# LAN9254_A_P1.net
KiCad netlist of a schematic drawn in Altium Designer
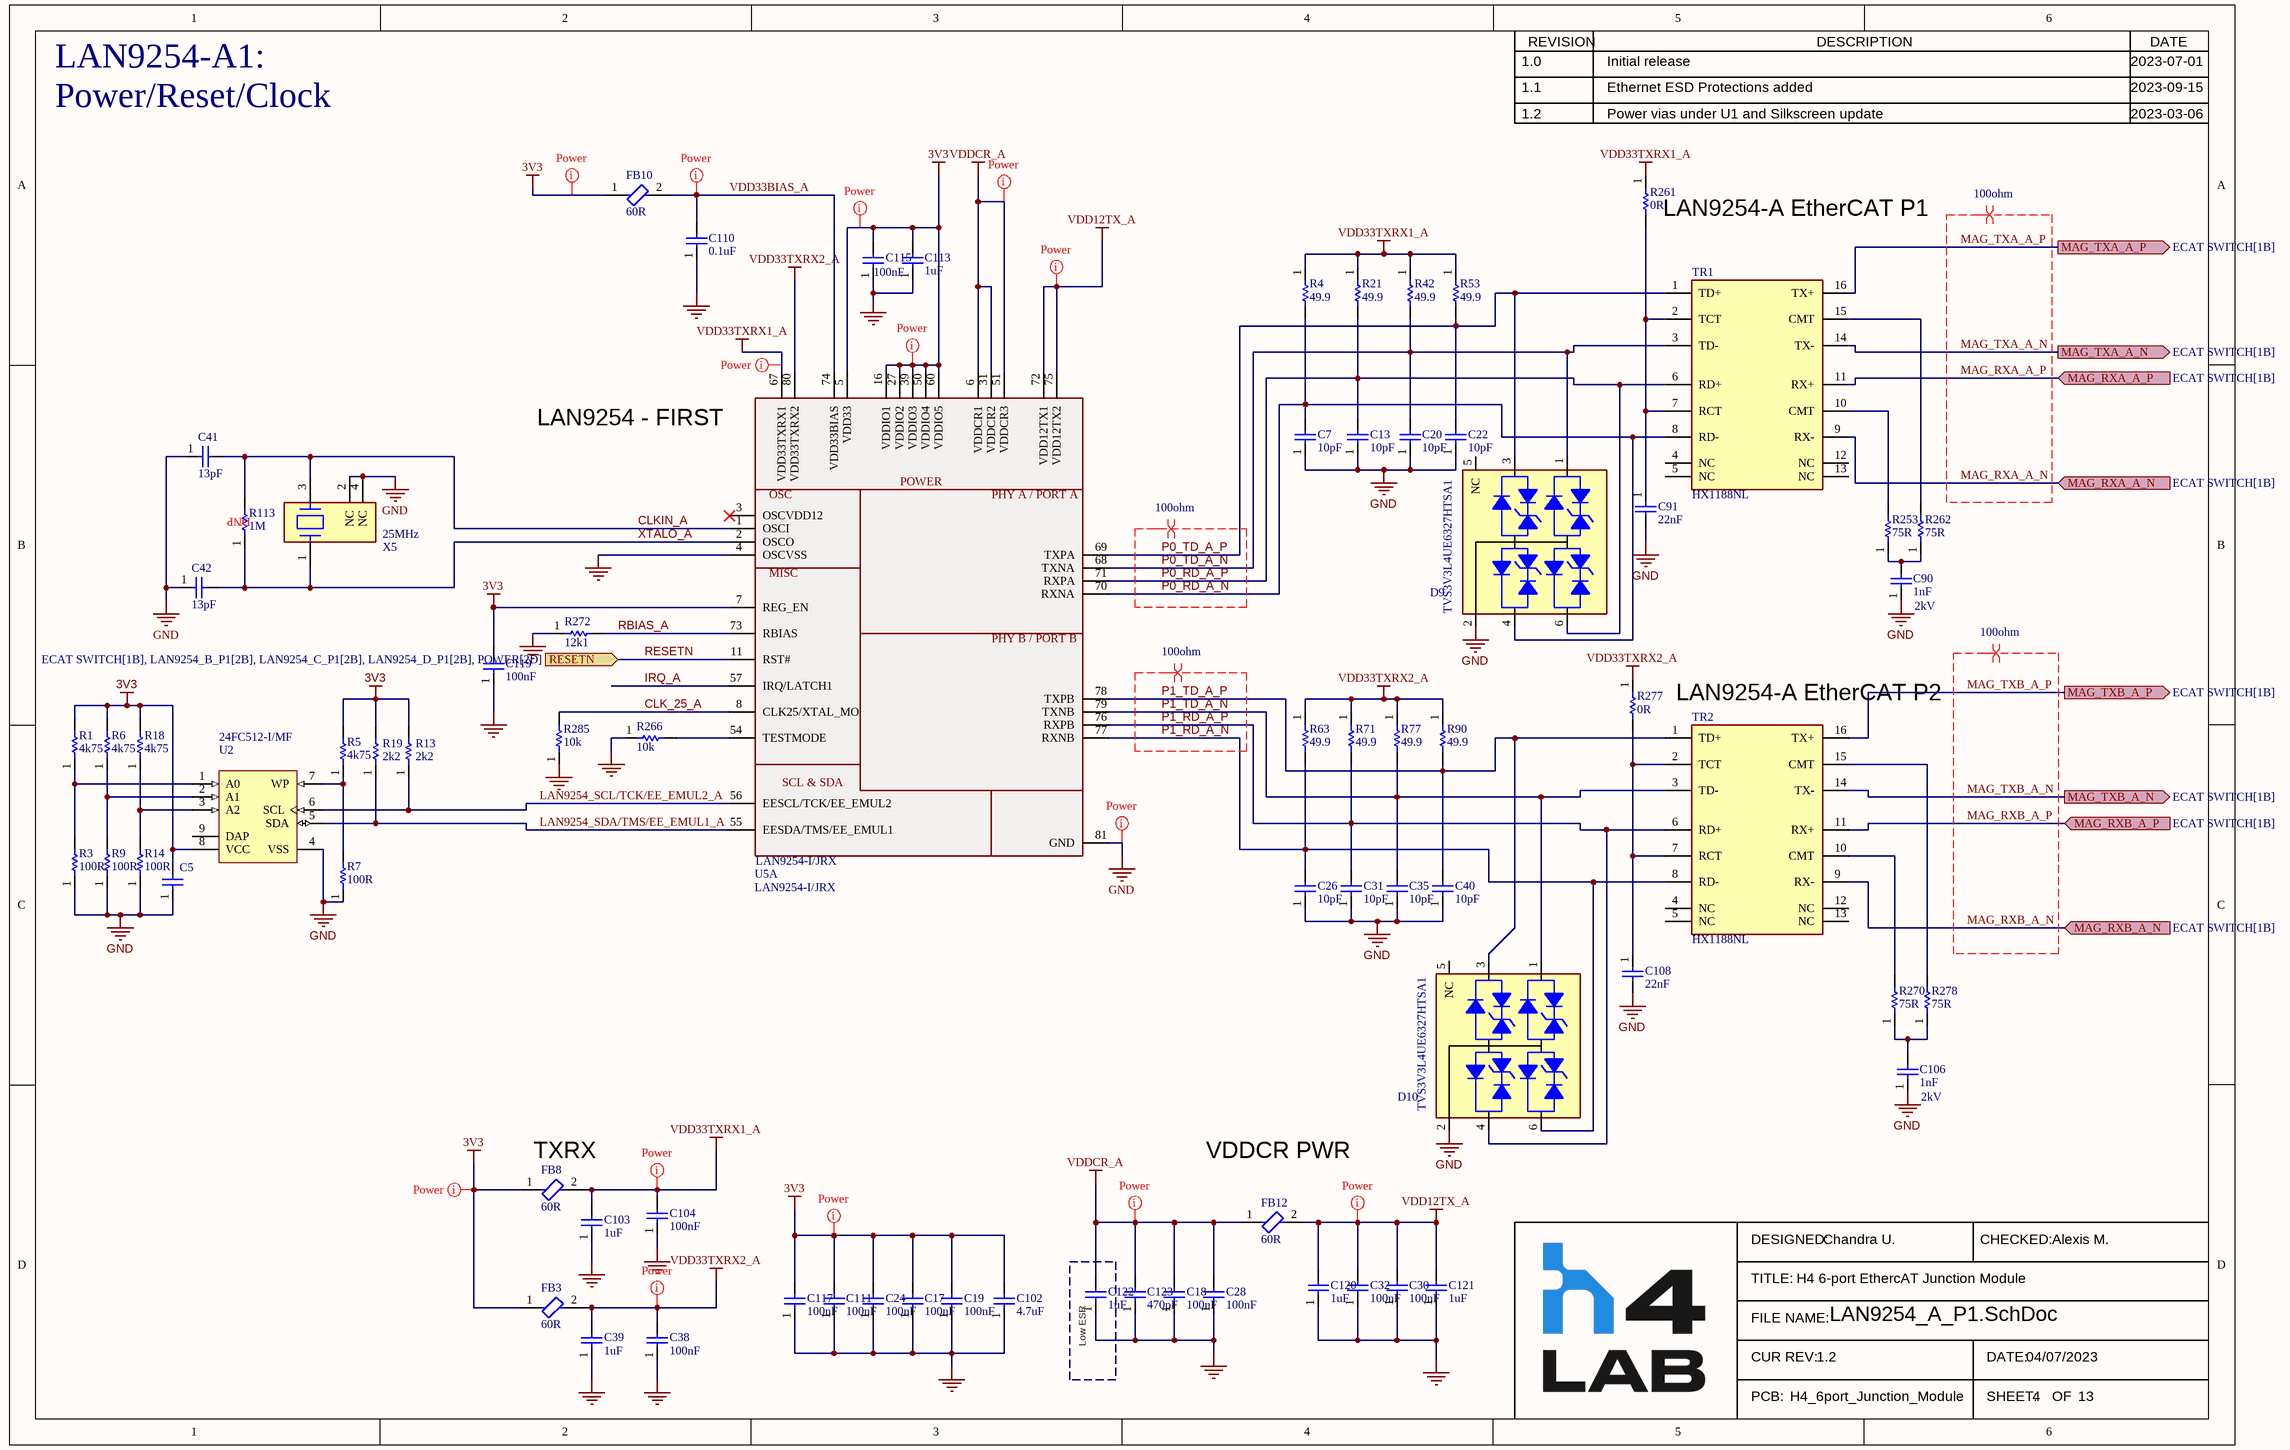
[diagram p0: LAN9254_A_P1.SchDoc]

(export (version "E")
  (design (tool "Eeschema 10.0.6"))
  (components
    (comp (ref "C5")
      (value "GRM155R71C104JA88D")
      (footprint "CAPC1005X03N(0402)")
      (description "CAP CER 0.1UF 16V X7R 0402")
      (fields (field (name "TOLERANCE") "5%"))
      (libsource (lib "IHMC_Altium_Lib") (part "100nF_16V_0402_CAP"))
    )
    (comp (ref "C7")
      (value "10pF")
      (footprint "0402_C")
      (description "Cap Ceramic 10pF 50V C0G 5% SMD 0402 125°C Punched Paper T/R")
      (fields (field (name "TOLERANCE") "5%") (field (name "MANUFACTURER") "KEMET"))
      (libsource (lib "IHMC_Altium_Lib") (part "10pF_50V_0402_C0402C100J5GAC7411"))
    )
    (comp (ref "C13")
      (value "10pF")
      (footprint "0402_C")
      (description "Cap Ceramic 10pF 50V C0G 5% SMD 0402 125°C Punched Paper T/R")
      (fields (field (name "TOLERANCE") "5%") (field (name "MANUFACTURER") "KEMET"))
      (libsource (lib "IHMC_Altium_Lib") (part "10pF_50V_0402_C0402C100J5GAC7411"))
    )
    (comp (ref "C17")
      (value "100nF")
      (footprint "CAPC1005X03N(0402)")
      (description "CAP CER 0.1UF 16V X7R 0402")
      (fields (field (name "MPN") "GRM155R71C104JA88D") (field (name "TOLERANCE") "5%"))
      (libsource (lib "IHMC_Altium_Lib") (part "100nF_16V_0402_CAP"))
    )
    (comp (ref "C18")
      (value "100nF")
      (footprint "CAPC1005X03N(0402)")
      (description "CAP CER 0.1UF 16V X7R 0402")
      (fields (field (name "MPN") "GRM155R71C104JA88D") (field (name "TOLERANCE") "5%"))
      (libsource (lib "IHMC_Altium_Lib") (part "100nF_16V_0402_CAP"))
    )
    (comp (ref "C19")
      (value "100nF")
      (footprint "CAPC1005X03N(0402)")
      (description "CAP CER 0.1UF 16V X7R 0402")
      (fields (field (name "MPN") "GRM155R71C104JA88D") (field (name "TOLERANCE") "5%"))
      (libsource (lib "IHMC_Altium_Lib") (part "100nF_16V_0402_CAP"))
    )
    (comp (ref "C20")
      (value "10pF")
      (footprint "0402_C")
      (description "Cap Ceramic 10pF 50V C0G 5% SMD 0402 125°C Punched Paper T/R")
      (fields (field (name "TOLERANCE") "5%") (field (name "MANUFACTURER") "KEMET"))
      (libsource (lib "IHMC_Altium_Lib") (part "10pF_50V_0402_C0402C100J5GAC7411"))
    )
    (comp (ref "C22")
      (value "10pF")
      (footprint "0402_C")
      (description "Cap Ceramic 10pF 50V C0G 5% SMD 0402 125°C Punched Paper T/R")
      (fields (field (name "TOLERANCE") "5%") (field (name "MANUFACTURER") "KEMET"))
      (libsource (lib "IHMC_Altium_Lib") (part "10pF_50V_0402_C0402C100J5GAC7411"))
    )
    (comp (ref "C24")
      (value "100nF")
      (footprint "CAPC1005X03N(0402)")
      (description "CAP CER 0.1UF 16V X7R 0402")
      (fields (field (name "MPN") "GRM155R71C104JA88D") (field (name "TOLERANCE") "5%"))
      (libsource (lib "IHMC_Altium_Lib") (part "100nF_16V_0402_CAP"))
    )
    (comp (ref "C26")
      (value "10pF")
      (footprint "0402_C")
      (description "Cap Ceramic 10pF 50V C0G 5% SMD 0402 125°C Punched Paper T/R")
      (fields (field (name "TOLERANCE") "5%") (field (name "MANUFACTURER") "KEMET"))
      (libsource (lib "IHMC_Altium_Lib") (part "10pF_50V_0402_C0402C100J5GAC7411"))
    )
    (comp (ref "C28")
      (value "100nF")
      (footprint "CAPC1005X03N(0402)")
      (description "CAP CER 0.1UF 16V X7R 0402")
      (fields (field (name "MPN") "GRM155R71C104JA88D") (field (name "TOLERANCE") "5%"))
      (libsource (lib "IHMC_Altium_Lib") (part "100nF_16V_0402_CAP"))
    )
    (comp (ref "C30")
      (value "100nF")
      (footprint "CAPC1005X03N(0402)")
      (description "CAP CER 0.1UF 16V X7R 0402")
      (fields (field (name "MPN") "GRM155R71C104JA88D") (field (name "TOLERANCE") "5%"))
      (libsource (lib "IHMC_Altium_Lib") (part "100nF_16V_0402_CAP"))
    )
    (comp (ref "C31")
      (value "10pF")
      (footprint "0402_C")
      (description "Cap Ceramic 10pF 50V C0G 5% SMD 0402 125°C Punched Paper T/R")
      (fields (field (name "TOLERANCE") "5%") (field (name "MANUFACTURER") "KEMET"))
      (libsource (lib "IHMC_Altium_Lib") (part "10pF_50V_0402_C0402C100J5GAC7411"))
    )
    (comp (ref "C32")
      (value "100nF")
      (footprint "CAPC1005X03N(0402)")
      (description "CAP CER 0.1UF 16V X7R 0402")
      (fields (field (name "MPN") "GRM155R71C104JA88D") (field (name "TOLERANCE") "5%"))
      (libsource (lib "IHMC_Altium_Lib") (part "100nF_16V_0402_CAP"))
    )
    (comp (ref "C35")
      (value "10pF")
      (footprint "0402_C")
      (description "Cap Ceramic 10pF 50V C0G 5% SMD 0402 125°C Punched Paper T/R")
      (fields (field (name "TOLERANCE") "5%") (field (name "MANUFACTURER") "KEMET"))
      (libsource (lib "IHMC_Altium_Lib") (part "10pF_50V_0402_C0402C100J5GAC7411"))
    )
    (comp (ref "C38")
      (value "100nF")
      (footprint "CAPC1005X03N(0402)")
      (description "CAP CER 0.1UF 16V X7R 0402")
      (fields (field (name "MPN") "GRM155R71C104JA88D") (field (name "TOLERANCE") "5%"))
      (libsource (lib "IHMC_Altium_Lib") (part "100nF_16V_0402_CAP"))
    )
    (comp (ref "C39")
      (value "1uF")
      (footprint "CAPC1608X09N(0603)")
      (description "MLCC - SMD/SMT 25volts 1uF X5R 10%")
      (fields
        (field (name "MPN") "C0603C105K3PACTU")
        (field (name "VOLTAGE") "25VDC")
        (field (name "DRAWN BY") "TC")
      )
      (libsource (lib "IHMC_Altium_Lib") (part "1uF_25VDC_0603_Cap"))
    )
    (comp (ref "C40")
      (value "10pF")
      (footprint "0402_C")
      (description "Cap Ceramic 10pF 50V C0G 5% SMD 0402 125°C Punched Paper T/R")
      (fields (field (name "TOLERANCE") "5%") (field (name "MANUFACTURER") "KEMET"))
      (libsource (lib "IHMC_Altium_Lib") (part "10pF_50V_0402_C0402C100J5GAC7411"))
    )
    (comp (ref "C41")
      (value "13pF")
      (footprint "0402_C")
      (description "Cap Ceramic Monolithic 13pF 50VDC 2% SMD Emboss T/R")
      (fields
        (field (name "MANUFACTURER") "Murata")
        (field (name "MANUFACTURER PART NUMBER") "GRM0225C1H130GA03L")
      )
      (libsource (lib "IHMC_Capacitors") (part "13pF_50V_0402_CAP_GRM0225C1H130GA03L"))
    )
    (comp (ref "C42")
      (value "13pF")
      (footprint "0402_C")
      (description "Cap Ceramic Monolithic 13pF 50VDC 2% SMD Emboss T/R")
      (fields
        (field (name "MANUFACTURER") "Murata")
        (field (name "MANUFACTURER PART NUMBER") "GRM0225C1H130GA03L")
      )
      (libsource (lib "IHMC_Capacitors") (part "13pF_50V_0402_CAP_GRM0225C1H130GA03L"))
    )
    (comp (ref "C90")
      (value "1nF")
      (footprint "CAPC3216X16N(1206)")
      (description "CAP CER 1000PF 2KV X7R 1206")
      (fields
        (field (name "VOLTAGE RATING") "2kV")
        (field (name "TOLERANCE") "10%")
        (field (name "MPN") "CC1206KKX7RDBB102")
      )
      (libsource (lib "IHMC_Altium_Lib") (part "1nF_2kV_1206_CAP"))
    )
    (comp (ref "C91")
      (value "22nF")
      (footprint "CAPC1005X03N(0402)")
      (description "CAP CER 0.022UF 50V X7R 0402")
      (fields (field (name "MPN") "GCM155R71H223KA55D") (field (name "TOLERANCE") "10%"))
      (libsource (lib "IHMC_Capacitors") (part "22nF_50V_0402_CAP"))
    )
    (comp (ref "C102")
      (value "4.7uF")
      (footprint "CAPC3216X16N(1206)")
      (description "CAP CER 4.7UF 50V X7R 1206")
      (fields (field (name "MPN") "CL31B475KBHNNNE") (field (name "TOLERANCE") "10%"))
      (libsource (lib "IHMC_Altium_Lib") (part "4.7uF_50V_1206_CAP"))
    )
    (comp (ref "C103")
      (value "1uF")
      (footprint "CAPC1608X09N(0603)")
      (description "MLCC - SMD/SMT 25volts 1uF X5R 10%")
      (fields
        (field (name "MPN") "C0603C105K3PACTU")
        (field (name "VOLTAGE") "25VDC")
        (field (name "DRAWN BY") "TC")
      )
      (libsource (lib "IHMC_Altium_Lib") (part "1uF_25VDC_0603_Cap"))
    )
    (comp (ref "C104")
      (value "100nF")
      (footprint "CAPC1005X03N(0402)")
      (description "CAP CER 0.1UF 16V X7R 0402")
      (fields (field (name "MPN") "GRM155R71C104JA88D") (field (name "TOLERANCE") "5%"))
      (libsource (lib "IHMC_Altium_Lib") (part "100nF_16V_0402_CAP"))
    )
    (comp (ref "C106")
      (value "1nF")
      (footprint "CAPC3216X16N(1206)")
      (description "CAP CER 1000PF 2KV X7R 1206")
      (fields
        (field (name "VOLTAGE RATING") "2kV")
        (field (name "TOLERANCE") "10%")
        (field (name "MPN") "CC1206KKX7RDBB102")
      )
      (libsource (lib "IHMC_Altium_Lib") (part "1nF_2kV_1206_CAP"))
    )
    (comp (ref "C108")
      (value "22nF")
      (footprint "CAPC1005X03N(0402)")
      (description "CAP CER 0.022UF 50V X7R 0402")
      (fields (field (name "MPN") "GCM155R71H223KA55D") (field (name "TOLERANCE") "10%"))
      (libsource (lib "IHMC_Capacitors") (part "22nF_50V_0402_CAP"))
    )
    (comp (ref "C110")
      (value "0.1uF")
      (footprint "CAPC1608X09N(0603)")
      (description "CAP CER 0.1UF 100V X7R 0603")
      (fields (field (name "MPN") "CL10B104KC8NNNC") (field (name "TOLERANCE") "10%"))
      (libsource (lib "IHMC_Altium_Lib") (part "0.1uF_100V_0603_CAP"))
    )
    (comp (ref "C111")
      (value "100nF")
      (footprint "CAPC1005X03N(0402)")
      (description "CAP CER 0.1UF 16V X7R 0402")
      (fields (field (name "MPN") "GRM155R71C104JA88D") (field (name "TOLERANCE") "5%"))
      (libsource (lib "IHMC_Altium_Lib") (part "100nF_16V_0402_CAP"))
    )
    (comp (ref "C113")
      (value "1uF")
      (footprint "0603_C")
      (description "Multilayer Ceramic Capacitors (High dielectric type), 10V, 1 uF, ± 10 %, 0603, X5R, RoHS")
      (fields (field (name "TOLERANCE") "10%") (field (name "MANUFACTURER") "Taiyo Yuden"))
      (libsource (lib "IHMC_Capacitors") (part "1uF_10V_low_ESR_0603_LMK107BJ105KA-T"))
    )
    (comp (ref "C115")
      (value "100nF")
      (footprint "CAPC1005X03N(0402)")
      (description "CAP CER 0.1UF 16V X7R 0402")
      (fields (field (name "MPN") "GRM155R71C104JA88D") (field (name "TOLERANCE") "5%"))
      (libsource (lib "IHMC_Altium_Lib") (part "100nF_16V_0402_CAP"))
    )
    (comp (ref "C117")
      (value "100nF")
      (footprint "CAPC1005X03N(0402)")
      (description "CAP CER 0.1UF 16V X7R 0402")
      (fields (field (name "MPN") "GRM155R71C104JA88D") (field (name "TOLERANCE") "5%"))
      (libsource (lib "IHMC_Altium_Lib") (part "100nF_16V_0402_CAP"))
    )
    (comp (ref "C119")
      (value "100nF")
      (footprint "CAPC1005X03N(0402)")
      (description "CAP CER 0.1UF 16V X7R 0402")
      (fields (field (name "MPN") "GRM155R71C104JA88D") (field (name "TOLERANCE") "5%"))
      (libsource (lib "IHMC_Altium_Lib") (part "100nF_16V_0402_CAP"))
    )
    (comp (ref "C120")
      (value "1uF")
      (footprint "CAPC1608X09N(0603)")
      (description "MLCC - SMD/SMT 25volts 1uF X5R 10%")
      (fields
        (field (name "MPN") "C0603C105K3PACTU")
        (field (name "VOLTAGE") "25VDC")
        (field (name "DRAWN BY") "TC")
      )
      (libsource (lib "IHMC_Altium_Lib") (part "1uF_25VDC_0603_Cap"))
    )
    (comp (ref "C121")
      (value "1uF")
      (footprint "CAPC1608X09N(0603)")
      (description "MLCC - SMD/SMT 25volts 1uF X5R 10%")
      (fields
        (field (name "MPN") "C0603C105K3PACTU")
        (field (name "TOLERANCE") "10%")
        (field (name "DRAWN BY") "TC")
      )
      (libsource (lib "IHMC_Altium_Lib") (part "1uF_25VDC_0603_Cap"))
    )
    (comp (ref "C122")
      (value "1uF")
      (footprint "0603_C")
      (description "Multilayer Ceramic Capacitors (High dielectric type), 10V, 1 uF, ± 10 %, 0603, X5R, RoHS")
      (fields (field (name "TOLERANCE") "10%") (field (name "MANUFACTURER") "Taiyo Yuden"))
      (libsource (lib "IHMC_Capacitors") (part "1uF_10V_low_ESR_0603_LMK107BJ105KA-T"))
    )
    (comp (ref "C123")
      (value "470pF")
      (footprint "CAPC1005X03N(0402)")
      (description "CAP CER 470PF 50V C0G/NP0 0402")
      (fields (field (name "MPN") "GCM1555C1H471JA16D") (field (name "VOLTAGE") "50V"))
      (libsource (lib "IHMC_Altium_Lib") (part "470pF_50V_0402_CAP"))
    )
    (comp (ref "D9")
      (value "TVS3V3L4UE6327HTSA1")
      (footprint "FP-SOT457-MFG")
      (description "Trans Voltage Suppressor Diode, 3.3V V(RWM), Unidirectional, 4 Element, Silicon")
      (fields (field (name "MANUFACTURER") "Infineon"))
      (libsource (lib "IHMC_Altium_Lib") (part "TVS_DIODE_ETHERCAT_PHY_7.7V_20A_TVS3V3L4UE6327HTSA1"))
    )
    (comp (ref "D10")
      (value "TVS3V3L4UE6327HTSA1")
      (footprint "FP-SOT457-MFG")
      (description "Trans Voltage Suppressor Diode, 3.3V V(RWM), Unidirectional, 4 Element, Silicon")
      (fields (field (name "MANUFACTURER") "Infineon"))
      (libsource (lib "IHMC_Altium_Lib") (part "TVS_DIODE_ETHERCAT_PHY_7.7V_20A_TVS3V3L4UE6327HTSA1"))
    )
    (comp (ref "FB3")
      (value "BKP2125HS600-T")
      (footprint "FP-BKP2125-IPC_C")
      (fields
        (field (name "TOLERANCE") "25%")
        (field (name "MANUFACTURER") "Taiyo Yuden")
        (field (name "IMPEDANCE") "60R")
      )
      (libsource (lib "IHMC_Altium_Lib") (part "60R_100Mhz_0805_3A"))
    )
    (comp (ref "FB8")
      (value "BKP2125HS600-T")
      (footprint "FP-BKP2125-IPC_C")
      (fields
        (field (name "TOLERANCE") "25%")
        (field (name "MANUFACTURER") "Taiyo Yuden")
        (field (name "IMPEDANCE") "60R")
      )
      (libsource (lib "IHMC_Altium_Lib") (part "60R_100Mhz_0805_3A"))
    )
    (comp (ref "FB10")
      (value "BKP2125HS600-T")
      (footprint "FP-BKP2125-IPC_C")
      (fields
        (field (name "TOLERANCE") "25%")
        (field (name "MANUFACTURER") "Taiyo Yuden")
        (field (name "IMPEDANCE") "60R")
      )
      (libsource (lib "IHMC_Altium_Lib") (part "60R_100Mhz_0805_3A"))
    )
    (comp (ref "FB12")
      (value "BKP2125HS600-T")
      (footprint "FP-BKP2125-IPC_C")
      (fields
        (field (name "TOLERANCE") "25%")
        (field (name "MANUFACTURER") "Taiyo Yuden")
        (field (name "IMPEDANCE") "60R")
      )
      (libsource (lib "IHMC_Altium_Lib") (part "60R_100Mhz_0805_3A"))
    )
    (comp (ref "R1")
      (value "4k75")
      (footprint "RESC1005X06N(0402)")
      (description "RES SMD 4.75K OHM 1% 1/16W 0402")
      (fields (field (name "MPN") "RC0402FR-074K75L") (field (name "POWER") "1/16"))
      (libsource (lib "IHMC_Altium_Lib") (part "4k75_1/16_0402_RES"))
    )
    (comp (ref "R3")
      (value "100R")
      (footprint "0402")
      (description "Res Thick Film 0402 100 Ohm 1% 0.063W(1/16W) ±200ppm/C Pad SMD Automotive T/R")
      (fields
        (field (name "MANUFACTURER") "TE Connectivity")
        (field (name "MANUFACTURER PART NUMBER") "CRGCQ0402F100R")
      )
      (libsource (lib "IHMC_Altium_Lib") (part "100R_1/16_0402_RES"))
    )
    (comp (ref "R4")
      (value "49.9")
      (footprint "RESC1005X06N(0402)")
      (description "RES SMD 49.9 OHM 1% 1/16W 0402")
      (fields
        (field (name "MPN") "CRCW040249R9FKED")
        (field (name "TOLERANCE") "1%")
        (field (name "DRAWN BY") "TC")
      )
      (libsource (lib "IHMC_Altium_Lib") (part "49R9_1/10W_0402_RES"))
    )
    (comp (ref "R5")
      (value "4k75")
      (footprint "RESC1005X06N(0402)")
      (description "RES SMD 4.75K OHM 1% 1/16W 0402")
      (fields (field (name "MPN") "RC0402FR-074K75L") (field (name "POWER") "1/16"))
      (libsource (lib "IHMC_Altium_Lib") (part "4k75_1/16_0402_RES"))
    )
    (comp (ref "R6")
      (value "4k75")
      (footprint "RESC1005X06N(0402)")
      (description "RES SMD 4.75K OHM 1% 1/16W 0402")
      (fields (field (name "MPN") "RC0402FR-074K75L") (field (name "POWER") "1/16"))
      (libsource (lib "IHMC_Altium_Lib") (part "4k75_1/16_0402_RES"))
    )
    (comp (ref "R7")
      (value "100R")
      (footprint "0402")
      (description "Res Thick Film 0402 100 Ohm 1% 0.063W(1/16W) ±200ppm/C Pad SMD Automotive T/R")
      (fields
        (field (name "MANUFACTURER") "TE Connectivity")
        (field (name "MANUFACTURER PART NUMBER") "CRGCQ0402F100R")
      )
      (libsource (lib "IHMC_Altium_Lib") (part "100R_1/16_0402_RES"))
    )
    (comp (ref "R9")
      (value "100R")
      (footprint "0402")
      (description "Res Thick Film 0402 100 Ohm 1% 0.063W(1/16W) ±200ppm/C Pad SMD Automotive T/R")
      (fields
        (field (name "MANUFACTURER") "TE Connectivity")
        (field (name "MANUFACTURER PART NUMBER") "CRGCQ0402F100R")
      )
      (libsource (lib "IHMC_Altium_Lib") (part "100R_1/16_0402_RES"))
    )
    (comp (ref "R13")
      (value "2k2")
      (footprint "0402")
      (description "Vishay CRCW Series Thick Film Resistor 0402 Case 2.2k 5% 0.063W 200ppm/K")
      (fields (field (name "TOLERANCE") "5%") (field (name "MANUFACTURER") "Vishay Dale"))
      (libsource (lib "IHMC_Altium_Lib") (part "2k2_1/16_0402_CRCW04022K20JNED_RES"))
    )
    (comp (ref "R14")
      (value "100R")
      (footprint "0402")
      (description "Res Thick Film 0402 100 Ohm 1% 0.063W(1/16W) ±200ppm/C Pad SMD Automotive T/R")
      (fields
        (field (name "MANUFACTURER") "TE Connectivity")
        (field (name "MANUFACTURER PART NUMBER") "CRGCQ0402F100R")
      )
      (libsource (lib "IHMC_Altium_Lib") (part "100R_1/16_0402_RES"))
    )
    (comp (ref "R18")
      (value "4k75")
      (footprint "RESC1005X06N(0402)")
      (description "RES SMD 4.75K OHM 1% 1/16W 0402")
      (fields (field (name "MPN") "RC0402FR-074K75L") (field (name "POWER") "1/16"))
      (libsource (lib "IHMC_Altium_Lib") (part "4k75_1/16_0402_RES"))
    )
    (comp (ref "R19")
      (value "2k2")
      (footprint "0402")
      (description "Vishay CRCW Series Thick Film Resistor 0402 Case 2.2k 5% 0.063W 200ppm/K")
      (fields (field (name "TOLERANCE") "5%") (field (name "MANUFACTURER") "Vishay Dale"))
      (libsource (lib "IHMC_Altium_Lib") (part "2k2_1/16_0402_CRCW04022K20JNED_RES"))
    )
    (comp (ref "R21")
      (value "49.9")
      (footprint "RESC1005X06N(0402)")
      (description "RES SMD 49.9 OHM 1% 1/16W 0402")
      (fields
        (field (name "MPN") "CRCW040249R9FKED")
        (field (name "TOLERANCE") "1%")
        (field (name "DRAWN BY") "TC")
      )
      (libsource (lib "IHMC_Altium_Lib") (part "49R9_1/10W_0402_RES"))
    )
    (comp (ref "R42")
      (value "49.9")
      (footprint "RESC1005X06N(0402)")
      (description "RES SMD 49.9 OHM 1% 1/16W 0402")
      (fields
        (field (name "MPN") "CRCW040249R9FKED")
        (field (name "TOLERANCE") "1%")
        (field (name "DRAWN BY") "TC")
      )
      (libsource (lib "IHMC_Altium_Lib") (part "49R9_1/10W_0402_RES"))
    )
    (comp (ref "R53")
      (value "49.9")
      (footprint "RESC1005X06N(0402)")
      (description "RES SMD 49.9 OHM 1% 1/16W 0402")
      (fields
        (field (name "MPN") "CRCW040249R9FKED")
        (field (name "TOLERANCE") "1%")
        (field (name "DRAWN BY") "TC")
      )
      (libsource (lib "IHMC_Altium_Lib") (part "49R9_1/10W_0402_RES"))
    )
    (comp (ref "R63")
      (value "49.9")
      (footprint "RESC1005X06N(0402)")
      (description "RES SMD 49.9 OHM 1% 1/16W 0402")
      (fields
        (field (name "MPN") "CRCW040249R9FKED")
        (field (name "TOLERANCE") "1%")
        (field (name "DRAWN BY") "TC")
      )
      (libsource (lib "IHMC_Altium_Lib") (part "49R9_1/10W_0402_RES"))
    )
    (comp (ref "R71")
      (value "49.9")
      (footprint "RESC1005X06N(0402)")
      (description "RES SMD 49.9 OHM 1% 1/16W 0402")
      (fields
        (field (name "MPN") "CRCW040249R9FKED")
        (field (name "TOLERANCE") "1%")
        (field (name "DRAWN BY") "TC")
      )
      (libsource (lib "IHMC_Altium_Lib") (part "49R9_1/10W_0402_RES"))
    )
    (comp (ref "R77")
      (value "49.9")
      (footprint "RESC1005X06N(0402)")
      (description "RES SMD 49.9 OHM 1% 1/16W 0402")
      (fields
        (field (name "MPN") "CRCW040249R9FKED")
        (field (name "TOLERANCE") "1%")
        (field (name "DRAWN BY") "TC")
      )
      (libsource (lib "IHMC_Altium_Lib") (part "49R9_1/10W_0402_RES"))
    )
    (comp (ref "R90")
      (value "49.9")
      (footprint "RESC1005X06N(0402)")
      (description "RES SMD 49.9 OHM 1% 1/16W 0402")
      (fields
        (field (name "MPN") "CRCW040249R9FKED")
        (field (name "TOLERANCE") "1%")
        (field (name "DRAWN BY") "TC")
      )
      (libsource (lib "IHMC_Altium_Lib") (part "49R9_1/10W_0402_RES"))
    )
    (comp (ref "R113")
      (value "1M")
      (footprint "RESC1608X09N(0603)")
      (description "RES SMD 1M OHM 1% 1/10W 0603")
      (fields (field (name "MPN") "RC0603FR-071ML") (field (name "TOLERANCE") "1%"))
      (libsource (lib "IHMC_Altium_Lib") (part "1M_1/10W_RES_0603"))
    )
    (comp (ref "R253")
      (value "75R")
      (footprint "RESC1005X06N(0402)")
      (description "RES SMD 75 OHM 1% 1/16W 0402")
      (fields
        (field (name "MPN") "CRCW040275R0FKEDC")
        (field (name "TOLERANCE") "+/-1%")
        (field (name "DRAWN BY") "TC")
      )
      (libsource (lib "IHMC_Altium_Lib") (part "75R_1/10W_0402_RES"))
    )
    (comp (ref "R261")
      (value "0R")
      (footprint "0402")
      (fields
        (field (name "MANUFACTURER") "Vishay Dale")
        (field (name "MANUFACTURER PART NUMBER") "RCS04020000Z0ED")
      )
      (libsource (lib "IHMC_Altium_Lib") (part "0R_1/5W_0402_RCS04020000Z0ED_RES"))
    )
    (comp (ref "R262")
      (value "75R")
      (footprint "RESC1005X06N(0402)")
      (description "RES SMD 75 OHM 1% 1/16W 0402")
      (fields
        (field (name "MPN") "CRCW040275R0FKEDC")
        (field (name "TOLERANCE") "+/-1%")
        (field (name "DRAWN BY") "TC")
      )
      (libsource (lib "IHMC_Altium_Lib") (part "75R_1/10W_0402_RES"))
    )
    (comp (ref "R266")
      (value "10k")
      (footprint "RESC1005X06N(0402)")
      (description "RES SMD 10K OHM 1% 1/16W 0402")
      (fields (field (name "TOLERANCE") "1%") (field (name "POWER") "1/16W"))
      (libsource (lib "IHMC_Resistors") (part "10k_1/16W_0402_RES"))
    )
    (comp (ref "R270")
      (value "75R")
      (footprint "RESC1005X06N(0402)")
      (description "RES SMD 75 OHM 1% 1/16W 0402")
      (fields
        (field (name "MPN") "CRCW040275R0FKEDC")
        (field (name "TOLERANCE") "+/-1%")
        (field (name "DRAWN BY") "TC")
      )
      (libsource (lib "IHMC_Altium_Lib") (part "75R_1/10W_0402_RES"))
    )
    (comp (ref "R272")
      (value "12k1")
      (footprint "RESC1005X06N(0402)")
      (description "RES SMD 12.1K OHM 1% 1/16W 0402")
      (fields (field (name "MPN") "RC0402FR-0712K1L") (field (name "TOLERANCE") "1%"))
      (libsource (lib "IHMC_Altium_Lib") (part "12k1_1/16W-0402_RES"))
    )
    (comp (ref "R277")
      (value "0R")
      (footprint "0402")
      (fields
        (field (name "MANUFACTURER") "Vishay Dale")
        (field (name "MANUFACTURER PART NUMBER") "RCS04020000Z0ED")
      )
      (libsource (lib "IHMC_Altium_Lib") (part "0R_1/5W_0402_RCS04020000Z0ED_RES"))
    )
    (comp (ref "R278")
      (value "75R")
      (footprint "RESC1005X06N(0402)")
      (description "RES SMD 75 OHM 1% 1/16W 0402")
      (fields
        (field (name "MPN") "CRCW040275R0FKEDC")
        (field (name "TOLERANCE") "+/-1%")
        (field (name "DRAWN BY") "TC")
      )
      (libsource (lib "IHMC_Altium_Lib") (part "75R_1/10W_0402_RES"))
    )
    (comp (ref "R285")
      (value "10k")
      (footprint "RESC1005X06N(0402)")
      (description "RES SMD 10K OHM 1% 1/16W 0402")
      (fields (field (name "TOLERANCE") "1%") (field (name "POWER") "1/16W"))
      (libsource (lib "IHMC_Resistors") (part "10k_1/16W_0402_RES"))
    )
    (comp (ref "TR1")
      (value "HX1188NL")
      (footprint "FP-HX1188NL-MFG")
      (description "Datacom Transformer, GENERAL PURPOSE Application(s), 1:1; 1:1")
      (fields (field (name "MANUFACTURER") "Pulse"))
      (libsource (lib "IHMC_Ethernet") (part "HX1188NL_TRANSFO_LAN_-40-85DEG"))
    )
    (comp (ref "TR2")
      (value "HX1188NL")
      (footprint "FP-HX1188NL-MFG")
      (description "Datacom Transformer, GENERAL PURPOSE Application(s), 1:1; 1:1")
      (fields (field (name "MANUFACTURER") "Pulse"))
      (libsource (lib "IHMC_Ethernet") (part "HX1188NL_TRANSFO_LAN_-40-85DEG"))
    )
    (comp (ref "U2")
      (value "24FC512-I/MF")
      (footprint "DFNS-MF8")
      (description "EEPROM Serial-2Wire 512K-bit 64K x 8 1.8V/2.5V/3.3V/5V 8-Pin DFN-S EP Tube")
      (fields (field (name "MANUFACTURER") "Microchip"))
      (libsource (lib "IHMC_Altium_Lib") (part "EEPROM_512kb_1MHz_24FC512-I/MF"))
    )
    (comp (ref "U5")
      (value "LAN9254-I/JRX")
      (footprint "QFP50P1400X1400X120-81N")
      (description "2/3-PORT Ethercat Slave Controller With 32 Digios With Integrated Ethernet Phys")
      (fields (field (name "MANUFACTURER") "Microchip"))
      (libsource (lib "IHMC_Ethernet") (part "LAN9254-I/JRX"))
    )
    (comp (ref "X5")
      (value "XRCGB25M000F3A00R0")
      (footprint "FP-XRCGB-MFG")
      (description "Crystal 25MHz ±30ppm (Tol) ±35ppm (Stability) 6pF 100Ohm Automotive 4-Pin SMD T/R")
      (fields (field (name "FREQUENCY") "25MHz") (field (name "MANUFACTURER") "Murata"))
      (libsource (lib "IHMC_Altium_Lib") (part "25MHz_Crystal_2016_35PPM_XRCGB25M000F3A00R0"))
    )
  )
  (nets
    (net (code "1") (name "/CLKIN_A") (class "Default")
      (node (ref "C41") (pin "2") (pinfunction "2_2") (pintype "passive"))
      (node (ref "R113") (pin "2") (pinfunction "2_2") (pintype "passive"))
      (node (ref "U5") (pin "1") (pinfunction "OSCI_1") (pintype "passive"))
      (node (ref "X5") (pin "3") (pintype "passive"))
    )
    (net (code "2") (name "/CLK_25_A") (class "Default")
      (node (ref "R285") (pin "2") (pinfunction "2_2") (pintype "passive"))
      (node (ref "U5") (pin "8") (pinfunction "CLK25/XTAL_MO_8") (pintype "passive"))
    )
    (net (code "3") (name "/IRQ_A") (class "Default")
      (node (ref "U5") (pin "57") (pinfunction "IRQ/LATCH1_57") (pintype "passive"))
    )
    (net (code "4") (name "/LAN9254_SCL{slash}TCK{slash}EE_EMUL2_A") (class "Default")
      (node (ref "R13") (pin "1") (pinfunction "1_1") (pintype "passive"))
      (node (ref "U2") (pin "6") (pinfunction "SCL_6") (pintype "input"))
      (node (ref "U5") (pin "56") (pinfunction "EESCL/TCK/EE_EMUL2_56") (pintype "passive"))
    )
    (net (code "5") (name "/LAN9254_SDA{slash}TMS{slash}EE_EMUL1_A") (class "Default")
      (node (ref "R19") (pin "1") (pinfunction "1_1") (pintype "passive"))
      (node (ref "U2") (pin "5") (pinfunction "SDA_5") (pintype "bidirectional"))
      (node (ref "U5") (pin "55") (pinfunction "EESDA/TMS/EE_EMUL1_55") (pintype "passive"))
    )
    (net (code "6") (name "/MAG_RXA_A_N") (class "Default")
      (node (ref "TR1") (pin "9") (pinfunction "RX-_9") (pintype "passive"))
    )
    (net (code "7") (name "/MAG_RXA_A_P") (class "Default")
      (node (ref "TR1") (pin "11") (pinfunction "RX+_11") (pintype "passive"))
    )
    (net (code "8") (name "/MAG_RXB_A_N") (class "Default")
      (node (ref "TR2") (pin "9") (pinfunction "RX-_9") (pintype "passive"))
    )
    (net (code "9") (name "/MAG_RXB_A_P") (class "Default")
      (node (ref "TR2") (pin "11") (pinfunction "RX+_11") (pintype "passive"))
    )
    (net (code "10") (name "/MAG_TXA_A_N") (class "Default")
      (node (ref "TR1") (pin "14") (pinfunction "TX-_14") (pintype "passive"))
    )
    (net (code "11") (name "/MAG_TXA_A_P") (class "Default")
      (node (ref "TR1") (pin "16") (pinfunction "TX+_16") (pintype "passive"))
    )
    (net (code "12") (name "/MAG_TXB_A_N") (class "Default")
      (node (ref "TR2") (pin "14") (pinfunction "TX-_14") (pintype "passive"))
    )
    (net (code "13") (name "/MAG_TXB_A_P") (class "Default")
      (node (ref "TR2") (pin "16") (pinfunction "TX+_16") (pintype "passive"))
    )
    (net (code "14") (name "/P0_RD_A_N") (class "Default")
      (node (ref "C7") (pin "2") (pinfunction "2_2") (pintype "passive"))
      (node (ref "D9") (pin "4") (pinfunction "4_4") (pintype "passive"))
      (node (ref "R4") (pin "2") (pinfunction "2_2") (pintype "passive"))
      (node (ref "TR1") (pin "8") (pinfunction "RD-_8") (pintype "passive"))
      (node (ref "U5") (pin "70") (pinfunction "RXNA_70") (pintype "passive"))
    )
    (net (code "15") (name "/P0_RD_A_P") (class "Default")
      (node (ref "C13") (pin "2") (pinfunction "2_2") (pintype "passive"))
      (node (ref "D9") (pin "6") (pinfunction "6_6") (pintype "passive"))
      (node (ref "R21") (pin "2") (pinfunction "2_2") (pintype "passive"))
      (node (ref "TR1") (pin "6") (pinfunction "RD+_6") (pintype "passive"))
      (node (ref "U5") (pin "71") (pinfunction "RXPA_71") (pintype "passive"))
    )
    (net (code "16") (name "/P0_TD_A_N") (class "Default")
      (node (ref "C20") (pin "2") (pinfunction "2_2") (pintype "passive"))
      (node (ref "D9") (pin "1") (pinfunction "1_1") (pintype "passive"))
      (node (ref "R42") (pin "2") (pinfunction "2_2") (pintype "passive"))
      (node (ref "TR1") (pin "3") (pinfunction "TD-_3") (pintype "passive"))
      (node (ref "U5") (pin "68") (pinfunction "TXNA_68") (pintype "passive"))
    )
    (net (code "17") (name "/P0_TD_A_P") (class "Default")
      (node (ref "C22") (pin "2") (pinfunction "2_2") (pintype "passive"))
      (node (ref "D9") (pin "3") (pinfunction "3_3") (pintype "passive"))
      (node (ref "R53") (pin "2") (pinfunction "2_2") (pintype "passive"))
      (node (ref "TR1") (pin "1") (pinfunction "TD+_1") (pintype "passive"))
      (node (ref "U5") (pin "69") (pinfunction "TXPA_69") (pintype "passive"))
    )
    (net (code "18") (name "/P1_RD_A_N") (class "Default")
      (node (ref "C26") (pin "2") (pinfunction "2_2") (pintype "passive"))
      (node (ref "D10") (pin "6") (pinfunction "6_6") (pintype "passive"))
      (node (ref "R63") (pin "2") (pinfunction "2_2") (pintype "passive"))
      (node (ref "TR2") (pin "8") (pinfunction "RD-_8") (pintype "passive"))
      (node (ref "U5") (pin "77") (pinfunction "RXNB_77") (pintype "passive"))
    )
    (net (code "19") (name "/P1_RD_A_P") (class "Default")
      (node (ref "C31") (pin "2") (pinfunction "2_2") (pintype "passive"))
      (node (ref "D10") (pin "4") (pinfunction "4_4") (pintype "passive"))
      (node (ref "R71") (pin "2") (pinfunction "2_2") (pintype "passive"))
      (node (ref "TR2") (pin "6") (pinfunction "RD+_6") (pintype "passive"))
      (node (ref "U5") (pin "76") (pinfunction "RXPB_76") (pintype "passive"))
    )
    (net (code "20") (name "/P1_TD_A_N") (class "Default")
      (node (ref "C35") (pin "2") (pinfunction "2_2") (pintype "passive"))
      (node (ref "D10") (pin "1") (pinfunction "1_1") (pintype "passive"))
      (node (ref "R77") (pin "2") (pinfunction "2_2") (pintype "passive"))
      (node (ref "TR2") (pin "3") (pinfunction "TD-_3") (pintype "passive"))
      (node (ref "U5") (pin "79") (pinfunction "TXNB_79") (pintype "passive"))
    )
    (net (code "21") (name "/P1_TD_A_P") (class "Default")
      (node (ref "C40") (pin "2") (pinfunction "2_2") (pintype "passive"))
      (node (ref "D10") (pin "3") (pinfunction "3_3") (pintype "passive"))
      (node (ref "R90") (pin "2") (pinfunction "2_2") (pintype "passive"))
      (node (ref "TR2") (pin "1") (pinfunction "TD+_1") (pintype "passive"))
      (node (ref "U5") (pin "78") (pinfunction "TXPB_78") (pintype "passive"))
    )
    (net (code "22") (name "/RBIAS_A") (class "Default")
      (node (ref "R272") (pin "2") (pinfunction "2_2") (pintype "passive"))
      (node (ref "U5") (pin "73") (pinfunction "RBIAS_73") (pintype "passive"))
    )
    (net (code "23") (name "/RESETN") (class "Default")
      (node (ref "U5") (pin "11") (pinfunction "RST#_11") (pintype "passive"))
    )
    (net (code "24") (name "/VDD33BIAS_A") (class "Default")
      (node (ref "C110") (pin "2") (pinfunction "2_2") (pintype "passive"))
      (node (ref "FB10") (pin "2") (pinfunction "2_2") (pintype "passive"))
      (node (ref "U5") (pin "74") (pinfunction "VDD33BIAS_74") (pintype "passive"))
    )
    (net (code "25") (name "/XTALO_A") (class "Default")
      (node (ref "C42") (pin "2") (pinfunction "2_2") (pintype "passive"))
      (node (ref "R113") (pin "1") (pinfunction "1_1") (pintype "passive"))
      (node (ref "U5") (pin "2") (pinfunction "OSCO_2") (pintype "passive"))
      (node (ref "X5") (pin "1") (pintype "passive"))
    )
    (net (code "26") (name "3V3") (class "Default")
      (node (ref "C102") (pin "2") (pinfunction "2_2") (pintype "passive"))
      (node (ref "C111") (pin "2") (pinfunction "2_2") (pintype "passive"))
      (node (ref "C113") (pin "2") (pinfunction "2_2") (pintype "passive"))
      (node (ref "C115") (pin "2") (pinfunction "2_2") (pintype "passive"))
      (node (ref "C117") (pin "2") (pinfunction "2_2") (pintype "passive"))
      (node (ref "C119") (pin "2") (pinfunction "2_2") (pintype "passive"))
      (node (ref "C17") (pin "2") (pinfunction "2_2") (pintype "passive"))
      (node (ref "C19") (pin "2") (pinfunction "2_2") (pintype "passive"))
      (node (ref "C24") (pin "2") (pinfunction "2_2") (pintype "passive"))
      (node (ref "C5") (pin "2") (pinfunction "2_2") (pintype "passive"))
      (node (ref "FB10") (pin "1") (pinfunction "1_1") (pintype "passive"))
      (node (ref "FB3") (pin "1") (pinfunction "1_1") (pintype "passive"))
      (node (ref "FB8") (pin "1") (pinfunction "1_1") (pintype "passive"))
      (node (ref "R1") (pin "2") (pinfunction "2_2") (pintype "passive"))
      (node (ref "R13") (pin "2") (pinfunction "2_2") (pintype "passive"))
      (node (ref "R18") (pin "2") (pinfunction "2_2") (pintype "passive"))
      (node (ref "R19") (pin "2") (pinfunction "2_2") (pintype "passive"))
      (node (ref "R5") (pin "2") (pinfunction "2_2") (pintype "passive"))
      (node (ref "R6") (pin "2") (pinfunction "2_2") (pintype "passive"))
      (node (ref "U2") (pin "8") (pinfunction "VCC_8") (pintype "power_in"))
      (node (ref "U5") (pin "16") (pinfunction "VDDIO1_16") (pintype "passive"))
      (node (ref "U5") (pin "27") (pinfunction "VDDIO2_27") (pintype "passive"))
      (node (ref "U5") (pin "39") (pinfunction "VDDIO3_39") (pintype "passive"))
      (node (ref "U5") (pin "5") (pinfunction "VDD33_5") (pintype "passive"))
      (node (ref "U5") (pin "50") (pinfunction "VDDIO4_50") (pintype "passive"))
      (node (ref "U5") (pin "60") (pinfunction "VDDIO5_60") (pintype "passive"))
      (node (ref "U5") (pin "7") (pinfunction "REG_EN_7") (pintype "passive"))
    )
    (net (code "27") (name "GND") (class "Default")
      (node (ref "C102") (pin "1") (pinfunction "1_1") (pintype "passive"))
      (node (ref "C103") (pin "1") (pinfunction "1_1") (pintype "passive"))
      (node (ref "C104") (pin "1") (pinfunction "1_1") (pintype "passive"))
      (node (ref "C106") (pin "1") (pinfunction "1_1") (pintype "passive"))
      (node (ref "C108") (pin "2") (pinfunction "2_2") (pintype "passive"))
      (node (ref "C110") (pin "1") (pinfunction "1_1") (pintype "passive"))
      (node (ref "C111") (pin "1") (pinfunction "1_1") (pintype "passive"))
      (node (ref "C113") (pin "1") (pinfunction "1_1") (pintype "passive"))
      (node (ref "C115") (pin "1") (pinfunction "1_1") (pintype "passive"))
      (node (ref "C117") (pin "1") (pinfunction "1_1") (pintype "passive"))
      (node (ref "C119") (pin "1") (pinfunction "1_1") (pintype "passive"))
      (node (ref "C120") (pin "1") (pinfunction "1_1") (pintype "passive"))
      (node (ref "C121") (pin "1") (pinfunction "1_1") (pintype "passive"))
      (node (ref "C122") (pin "1") (pinfunction "1_1") (pintype "passive"))
      (node (ref "C123") (pin "1") (pinfunction "1_1") (pintype "passive"))
      (node (ref "C13") (pin "1") (pinfunction "1_1") (pintype "passive"))
      (node (ref "C17") (pin "1") (pinfunction "1_1") (pintype "passive"))
      (node (ref "C18") (pin "1") (pinfunction "1_1") (pintype "passive"))
      (node (ref "C19") (pin "1") (pinfunction "1_1") (pintype "passive"))
      (node (ref "C20") (pin "1") (pinfunction "1_1") (pintype "passive"))
      (node (ref "C22") (pin "1") (pinfunction "1_1") (pintype "passive"))
      (node (ref "C24") (pin "1") (pinfunction "1_1") (pintype "passive"))
      (node (ref "C26") (pin "1") (pinfunction "1_1") (pintype "passive"))
      (node (ref "C28") (pin "1") (pinfunction "1_1") (pintype "passive"))
      (node (ref "C30") (pin "1") (pinfunction "1_1") (pintype "passive"))
      (node (ref "C31") (pin "1") (pinfunction "1_1") (pintype "passive"))
      (node (ref "C32") (pin "1") (pinfunction "1_1") (pintype "passive"))
      (node (ref "C35") (pin "1") (pinfunction "1_1") (pintype "passive"))
      (node (ref "C38") (pin "1") (pinfunction "1_1") (pintype "passive"))
      (node (ref "C39") (pin "1") (pinfunction "1_1") (pintype "passive"))
      (node (ref "C40") (pin "1") (pinfunction "1_1") (pintype "passive"))
      (node (ref "C41") (pin "1") (pinfunction "1_1") (pintype "passive"))
      (node (ref "C42") (pin "1") (pinfunction "1_1") (pintype "passive"))
      (node (ref "C5") (pin "1") (pinfunction "1_1") (pintype "passive"))
      (node (ref "C7") (pin "1") (pinfunction "1_1") (pintype "passive"))
      (node (ref "C90") (pin "1") (pinfunction "1_1") (pintype "passive"))
      (node (ref "C91") (pin "2") (pinfunction "2_2") (pintype "passive"))
      (node (ref "D10") (pin "2") (pinfunction "GND_2") (pintype "power_in"))
      (node (ref "D9") (pin "2") (pinfunction "GND_2") (pintype "power_in"))
      (node (ref "R14") (pin "1") (pinfunction "1_1") (pintype "passive"))
      (node (ref "R266") (pin "1") (pinfunction "1_1") (pintype "passive"))
      (node (ref "R272") (pin "1") (pinfunction "1_1") (pintype "passive"))
      (node (ref "R285") (pin "1") (pinfunction "1_1") (pintype "passive"))
      (node (ref "R3") (pin "1") (pinfunction "1_1") (pintype "passive"))
      (node (ref "R7") (pin "1") (pinfunction "1_1") (pintype "passive"))
      (node (ref "R9") (pin "1") (pinfunction "1_1") (pintype "passive"))
      (node (ref "U2") (pin "4") (pinfunction "VSS_4") (pintype "power_in"))
      (node (ref "U5") (pin "4") (pinfunction "OSCVSS_4") (pintype "passive"))
      (node (ref "U5") (pin "81") (pinfunction "GND_81") (pintype "passive"))
      (node (ref "X5") (pin "2") (pinfunction "NC_2") (pintype "passive"))
      (node (ref "X5") (pin "4") (pinfunction "NC_4") (pintype "passive"))
    )
    (net (code "28") (name "Net-(C90-Pad2)") (class "Default")
      (node (ref "C90") (pin "2") (pinfunction "2_2") (pintype "passive"))
      (node (ref "R253") (pin "1") (pinfunction "1_1") (pintype "passive"))
      (node (ref "R262") (pin "1") (pinfunction "1_1") (pintype "passive"))
    )
    (net (code "29") (name "Net-(C106-Pad2)") (class "Default")
      (node (ref "C106") (pin "2") (pinfunction "2_2") (pintype "passive"))
      (node (ref "R270") (pin "1") (pinfunction "1_1") (pintype "passive"))
      (node (ref "R278") (pin "1") (pinfunction "1_1") (pintype "passive"))
    )
    (net (code "30") (name "Net-(R253-Pad2)") (class "Default")
      (node (ref "R253") (pin "2") (pinfunction "2_2") (pintype "passive"))
      (node (ref "TR1") (pin "10") (pinfunction "CMT_10") (pintype "passive"))
    )
    (net (code "31") (name "Net-(R262-Pad2)") (class "Default")
      (node (ref "R262") (pin "2") (pinfunction "2_2") (pintype "passive"))
      (node (ref "TR1") (pin "15") (pinfunction "CMT_15") (pintype "passive"))
    )
    (net (code "32") (name "Net-(R270-Pad2)") (class "Default")
      (node (ref "R270") (pin "2") (pinfunction "2_2") (pintype "passive"))
      (node (ref "TR2") (pin "10") (pinfunction "CMT_10") (pintype "passive"))
    )
    (net (code "33") (name "Net-(R278-Pad2)") (class "Default")
      (node (ref "R278") (pin "2") (pinfunction "2_2") (pintype "passive"))
      (node (ref "TR2") (pin "15") (pinfunction "CMT_15") (pintype "passive"))
    )
    (net (code "34") (name "Net-(TR1-RCT)") (class "Default")
      (node (ref "C91") (pin "1") (pinfunction "1_1") (pintype "passive"))
      (node (ref "R261") (pin "2") (pinfunction "2_2") (pintype "passive"))
      (node (ref "TR1") (pin "2") (pinfunction "TCT_2") (pintype "passive"))
      (node (ref "TR1") (pin "7") (pinfunction "RCT_7") (pintype "passive"))
    )
    (net (code "35") (name "Net-(TR2-RCT)") (class "Default")
      (node (ref "C108") (pin "1") (pinfunction "1_1") (pintype "passive"))
      (node (ref "R277") (pin "2") (pinfunction "2_2") (pintype "passive"))
      (node (ref "TR2") (pin "2") (pinfunction "TCT_2") (pintype "passive"))
      (node (ref "TR2") (pin "7") (pinfunction "RCT_7") (pintype "passive"))
    )
    (net (code "36") (name "Net-(U2-A0)") (class "Default")
      (node (ref "R1") (pin "1") (pinfunction "1_1") (pintype "passive"))
      (node (ref "R3") (pin "2") (pinfunction "2_2") (pintype "passive"))
      (node (ref "U2") (pin "1") (pinfunction "A0_1") (pintype "input"))
    )
    (net (code "37") (name "Net-(U2-A1)") (class "Default")
      (node (ref "R6") (pin "1") (pinfunction "1_1") (pintype "passive"))
      (node (ref "R9") (pin "2") (pinfunction "2_2") (pintype "passive"))
      (node (ref "U2") (pin "2") (pinfunction "A1_2") (pintype "input"))
    )
    (net (code "38") (name "Net-(U2-A2)") (class "Default")
      (node (ref "R14") (pin "2") (pinfunction "2_2") (pintype "passive"))
      (node (ref "R18") (pin "1") (pinfunction "1_1") (pintype "passive"))
      (node (ref "U2") (pin "3") (pinfunction "A2_3") (pintype "input"))
    )
    (net (code "39") (name "Net-(U2-WP)") (class "Default")
      (node (ref "R5") (pin "1") (pinfunction "1_1") (pintype "passive"))
      (node (ref "R7") (pin "2") (pinfunction "2_2") (pintype "passive"))
      (node (ref "U2") (pin "7") (pinfunction "WP_7") (pintype "input"))
    )
    (net (code "40") (name "Net-(U5A-TESTMODE)") (class "Default")
      (node (ref "R266") (pin "2") (pinfunction "2_2") (pintype "passive"))
      (node (ref "U5") (pin "54") (pinfunction "TESTMODE_54") (pintype "passive"))
    )
    (net (code "41") (name "VDD12TX_A") (class "Default")
      (node (ref "C120") (pin "2") (pinfunction "2_2") (pintype "passive"))
      (node (ref "C121") (pin "2") (pinfunction "2_2") (pintype "passive"))
      (node (ref "C30") (pin "2") (pinfunction "2_2") (pintype "passive"))
      (node (ref "C32") (pin "2") (pinfunction "2_2") (pintype "passive"))
      (node (ref "FB12") (pin "2") (pinfunction "2_2") (pintype "passive"))
      (node (ref "U5") (pin "72") (pinfunction "VDD12TX1_72") (pintype "passive"))
      (node (ref "U5") (pin "75") (pinfunction "VDD12TX2_75") (pintype "passive"))
    )
    (net (code "42") (name "VDD33TXRX1_A") (class "Default")
      (node (ref "C103") (pin "2") (pinfunction "2_2") (pintype "passive"))
      (node (ref "C104") (pin "2") (pinfunction "2_2") (pintype "passive"))
      (node (ref "FB8") (pin "2") (pinfunction "2_2") (pintype "passive"))
      (node (ref "R21") (pin "1") (pinfunction "1_1") (pintype "passive"))
      (node (ref "R261") (pin "1") (pinfunction "1_1") (pintype "passive"))
      (node (ref "R4") (pin "1") (pinfunction "1_1") (pintype "passive"))
      (node (ref "R42") (pin "1") (pinfunction "1_1") (pintype "passive"))
      (node (ref "R53") (pin "1") (pinfunction "1_1") (pintype "passive"))
      (node (ref "U5") (pin "67") (pinfunction "VDD33TXRX1_67") (pintype "passive"))
    )
    (net (code "43") (name "VDD33TXRX2_A") (class "Default")
      (node (ref "C38") (pin "2") (pinfunction "2_2") (pintype "passive"))
      (node (ref "C39") (pin "2") (pinfunction "2_2") (pintype "passive"))
      (node (ref "FB3") (pin "2") (pinfunction "2_2") (pintype "passive"))
      (node (ref "R277") (pin "1") (pinfunction "1_1") (pintype "passive"))
      (node (ref "R63") (pin "1") (pinfunction "1_1") (pintype "passive"))
      (node (ref "R71") (pin "1") (pinfunction "1_1") (pintype "passive"))
      (node (ref "R77") (pin "1") (pinfunction "1_1") (pintype "passive"))
      (node (ref "R90") (pin "1") (pinfunction "1_1") (pintype "passive"))
      (node (ref "U5") (pin "80") (pinfunction "VDD33TXRX2_80") (pintype "passive"))
    )
    (net (code "44") (name "VDDCR_A") (class "Default")
      (node (ref "C122") (pin "2") (pinfunction "2_2") (pintype "passive"))
      (node (ref "C123") (pin "2") (pinfunction "2_2") (pintype "passive"))
      (node (ref "C18") (pin "2") (pinfunction "2_2") (pintype "passive"))
      (node (ref "C28") (pin "2") (pinfunction "2_2") (pintype "passive"))
      (node (ref "FB12") (pin "1") (pinfunction "1_1") (pintype "passive"))
      (node (ref "U5") (pin "31") (pinfunction "VDDCR2_31") (pintype "passive"))
      (node (ref "U5") (pin "51") (pinfunction "VDDCR3_51") (pintype "passive"))
      (node (ref "U5") (pin "6") (pinfunction "VDDCR1_6") (pintype "passive"))
    )
    (net (code "45") (name "unconnected-(D9-NC-Pad5)") (class "Default")
      (node (ref "D9") (pin "5") (pinfunction "NC_5") (pintype "passive"))
    )
    (net (code "46") (name "unconnected-(D10-NC-Pad5)") (class "Default")
      (node (ref "D10") (pin "5") (pinfunction "NC_5") (pintype "passive"))
    )
    (net (code "47") (name "unconnected-(TR1-NC-Pad4)") (class "Default")
      (node (ref "TR1") (pin "4") (pinfunction "NC_4") (pintype "passive"))
    )
    (net (code "48") (name "unconnected-(TR1-NC-Pad5)") (class "Default")
      (node (ref "TR1") (pin "5") (pinfunction "NC_5") (pintype "passive"))
    )
    (net (code "49") (name "unconnected-(TR1-NC-Pad12)") (class "Default")
      (node (ref "TR1") (pin "12") (pinfunction "NC_12") (pintype "passive"))
    )
    (net (code "50") (name "unconnected-(TR1-NC-Pad13)") (class "Default")
      (node (ref "TR1") (pin "13") (pinfunction "NC_13") (pintype "passive"))
    )
    (net (code "51") (name "unconnected-(TR2-NC-Pad4)") (class "Default")
      (node (ref "TR2") (pin "4") (pinfunction "NC_4") (pintype "passive"))
    )
    (net (code "52") (name "unconnected-(TR2-NC-Pad5)") (class "Default")
      (node (ref "TR2") (pin "5") (pinfunction "NC_5") (pintype "passive"))
    )
    (net (code "53") (name "unconnected-(TR2-NC-Pad12)") (class "Default")
      (node (ref "TR2") (pin "12") (pinfunction "NC_12") (pintype "passive"))
    )
    (net (code "54") (name "unconnected-(TR2-NC-Pad13)") (class "Default")
      (node (ref "TR2") (pin "13") (pinfunction "NC_13") (pintype "passive"))
    )
    (net (code "55") (name "unconnected-(U2-DAP-Pad9)") (class "Default")
      (node (ref "U2") (pin "9") (pinfunction "DAP_9") (pintype "power_in"))
    )
    (net (code "56") (name "unconnected-(U5A-OSCVDD12-Pad3)") (class "Default")
      (node (ref "U5") (pin "3") (pinfunction "OSCVDD12_3") (pintype "passive+no_connect"))
    )
  )
)
